# deska.net
KiCad netlist of a schematic drawn in EAGLE
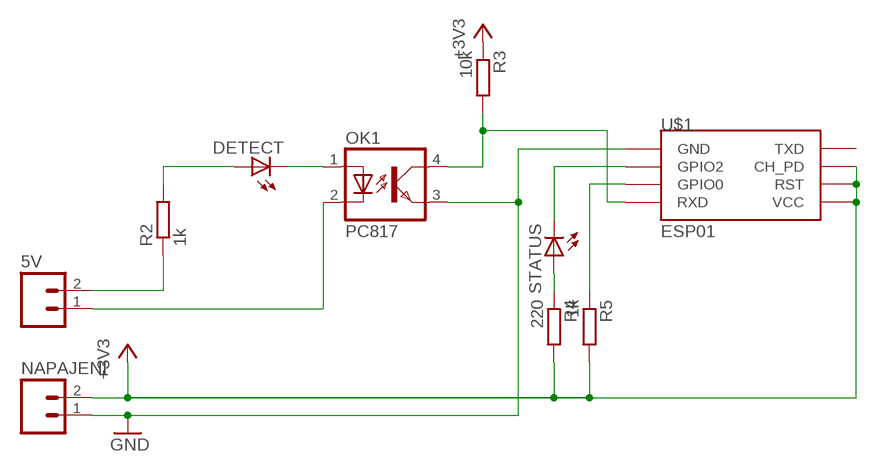
[diagram p0: schematic, sheet 1]

(export (version "E")
  (design (tool "Eeschema 10.0.6"))
  (components
    (comp (ref "5V")
      (value "M02")
      (footprint "eagle-import:02P")
      (libsource (lib "eagle-import") (part "M02"))
    )
    (comp (ref "DETECT")
      (value "LED3MM")
      (footprint "eagle-import:LED3MM")
      (libsource (lib "eagle-import") (part "LED3MM"))
    )
    (comp (ref "NAPAJENI")
      (value "M02")
      (footprint "eagle-import:02P")
      (libsource (lib "eagle-import") (part "M02"))
    )
    (comp (ref "OK1")
      (value "PC817")
      (footprint "eagle-import:DIL04")
      (fields (field (name "MPN") "PC817X4J000F"))
      (libsource (lib "eagle-import") (part "PC817"))
    )
    (comp (ref "R2")
      (value "1k")
      (footprint "eagle-import:0207_7")
      (libsource (lib "eagle-import") (part "R-EU_0207/7"))
    )
    (comp (ref "R3")
      (value "10k")
      (footprint "eagle-import:0207_7")
      (libsource (lib "eagle-import") (part "R-EU_0207/7"))
    )
    (comp (ref "R4")
      (value "220")
      (footprint "eagle-import:0207_7")
      (libsource (lib "eagle-import") (part "R-EU_0207/7"))
    )
    (comp (ref "R5")
      (value "1k")
      (footprint "eagle-import:0207_7")
      (libsource (lib "eagle-import") (part "R-EU_0207/7"))
    )
    (comp (ref "STATUS")
      (value "LED3MM")
      (footprint "eagle-import:LED3MM")
      (libsource (lib "eagle-import") (part "LED3MM"))
    )
    (comp (ref "U$1")
      (value "ESP01")
      (footprint "eagle-import:ESP01")
      (libsource (lib "eagle-import") (part "ESP01"))
    )
  )
  (nets
    (net (code "1") (name "+3V3") (class "Default")
      (node (ref "NAPAJENI") (pin "2") (pinfunction "2_2") (pintype "passive"))
      (node (ref "R3") (pin "1") (pinfunction "1_1") (pintype "passive"))
      (node (ref "R4") (pin "2") (pinfunction "2_2") (pintype "passive"))
      (node (ref "R5") (pin "2") (pinfunction "2_2") (pintype "passive"))
      (node (ref "U$1") (pin "CH_PD") (pinfunction "CH_PD_CH_PD") (pintype "bidirectional"))
      (node (ref "U$1") (pin "RST") (pinfunction "RST_RST") (pintype "bidirectional"))
      (node (ref "U$1") (pin "VCC") (pinfunction "VCC_VCC") (pintype "bidirectional"))
    )
    (net (code "2") (name "GND") (class "Default")
      (node (ref "NAPAJENI") (pin "1") (pinfunction "1_1") (pintype "passive"))
      (node (ref "OK1") (pin "3") (pinfunction "EMIT_3") (pintype "passive"))
      (node (ref "U$1") (pin "GND") (pinfunction "GND_GND") (pintype "bidirectional"))
    )
    (net (code "3") (name "Net-(5V-Pad2)") (class "Default")
      (node (ref "5V") (pin "2") (pinfunction "2_2") (pintype "passive"))
      (node (ref "R2") (pin "1") (pinfunction "1_1") (pintype "passive"))
    )
    (net (code "4") (name "Net-(DETECT-C)") (class "Default")
      (node (ref "DETECT") (pin "K") (pinfunction "C_K") (pintype "passive"))
      (node (ref "OK1") (pin "1") (pinfunction "A_1") (pintype "passive"))
    )
    (net (code "5") (name "Net-(DETECT-PadA)") (class "Default")
      (node (ref "DETECT") (pin "A") (pinfunction "A_A") (pintype "passive"))
      (node (ref "R2") (pin "2") (pinfunction "2_2") (pintype "passive"))
    )
    (net (code "6") (name "Net-(OK1-C)") (class "Default")
      (node (ref "5V") (pin "1") (pinfunction "1_1") (pintype "passive"))
      (node (ref "OK1") (pin "2") (pinfunction "C_2") (pintype "passive"))
    )
    (net (code "7") (name "Net-(OK1-COL)") (class "Default")
      (node (ref "OK1") (pin "4") (pinfunction "COL_4") (pintype "passive"))
      (node (ref "R3") (pin "2") (pinfunction "2_2") (pintype "passive"))
      (node (ref "U$1") (pin "RX") (pinfunction "RXD_RX") (pintype "bidirectional"))
    )
    (net (code "8") (name "Net-(R4-Pad1)") (class "Default")
      (node (ref "R4") (pin "1") (pinfunction "1_1") (pintype "passive"))
      (node (ref "STATUS") (pin "A") (pinfunction "A_A") (pintype "passive"))
    )
    (net (code "9") (name "Net-(R5-Pad1)") (class "Default")
      (node (ref "R5") (pin "1") (pinfunction "1_1") (pintype "passive"))
      (node (ref "U$1") (pin "GPIO0") (pinfunction "GPIO0_GPIO0") (pintype "bidirectional"))
    )
    (net (code "10") (name "Net-(STATUS-C)") (class "Default")
      (node (ref "STATUS") (pin "K") (pinfunction "C_K") (pintype "passive"))
      (node (ref "U$1") (pin "GPIO2") (pinfunction "GPIO2_GPIO2") (pintype "bidirectional"))
    )
    (net (code "11") (name "unconnected-(U$1-TXD-PadTX)") (class "Default")
      (node (ref "U$1") (pin "TX") (pinfunction "TXD_TX") (pintype "bidirectional"))
    )
  )
)
